# Sparkfun_MiP_ProMini-Pack.net
KiCad netlist of a schematic drawn in EAGLE
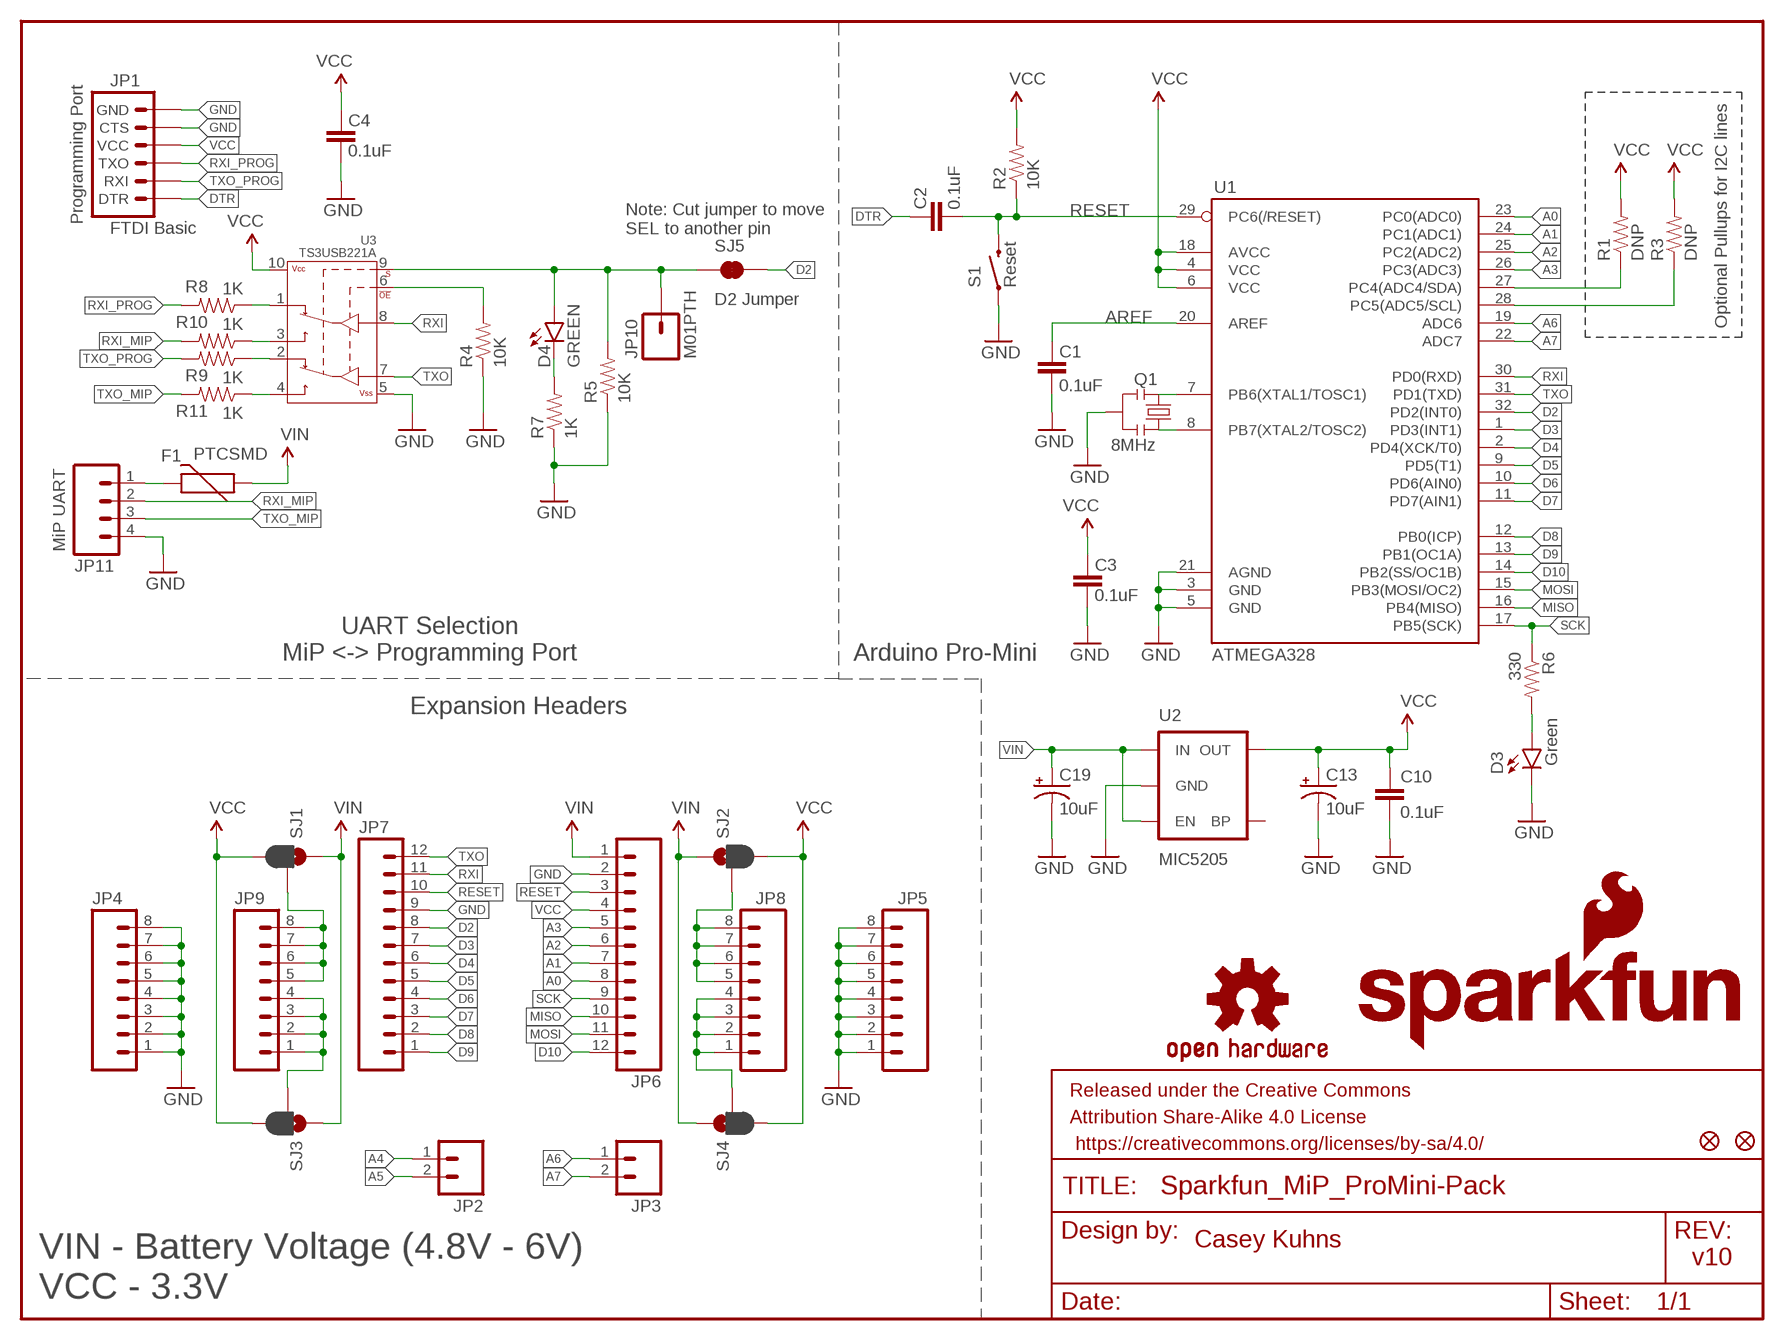
[diagram p0: schematic, sheet 1]

(export (version "E")
  (design (tool "Eeschema 10.0.6"))
  (components
    (comp (ref "C1")
      (value "0.1uF")
      (footprint "eagle-import:0603-CAP")
      (libsource (lib "eagle-import") (part "0.1UF-25V(+80/-20%)(0603)"))
    )
    (comp (ref "C2")
      (value "0.1uF")
      (footprint "eagle-import:0603-CAP")
      (libsource (lib "eagle-import") (part "0.1UF-25V(+80/-20%)(0603)"))
    )
    (comp (ref "C3")
      (value "0.1uF")
      (footprint "eagle-import:0603-CAP")
      (libsource (lib "eagle-import") (part "0.1UF-25V(+80/-20%)(0603)"))
    )
    (comp (ref "C4")
      (value "0.1uF")
      (footprint "eagle-import:0603-CAP")
      (libsource (lib "eagle-import") (part "0.1UF-25V(+80/-20%)(0603)"))
    )
    (comp (ref "C10")
      (value "0.1uF")
      (footprint "eagle-import:0603-CAP")
      (libsource (lib "eagle-import") (part "0.1UF-25V(+80/-20%)(0603)"))
    )
    (comp (ref "C13")
      (value "10uF")
      (footprint "eagle-import:EIA3216")
      (libsource (lib "eagle-import") (part "CAP_POL1206"))
    )
    (comp (ref "C19")
      (value "10uF")
      (footprint "eagle-import:EIA3216")
      (libsource (lib "eagle-import") (part "CAP_POL1206"))
    )
    (comp (ref "D3")
      (value "Green")
      (footprint "eagle-import:LED-0603")
      (libsource (lib "eagle-import") (part "LED-GREEN0603"))
    )
    (comp (ref "D4")
      (value "GREEN")
      (footprint "eagle-import:LED-0603")
      (libsource (lib "eagle-import") (part "LED-GREEN0603"))
    )
    (comp (ref "F1")
      (value "PTCSMD")
      (footprint "eagle-import:PTC-1206")
      (libsource (lib "eagle-import") (part "PTCSMD"))
    )
    (comp (ref "FID1")
      (value "FIDUCIAL1X2")
      (footprint "eagle-import:FIDUCIAL-1X2")
      (libsource (lib "eagle-import") (part "FIDUCIAL1X2"))
    )
    (comp (ref "FID2")
      (value "FIDUCIAL1X2")
      (footprint "eagle-import:FIDUCIAL-1X2")
      (libsource (lib "eagle-import") (part "FIDUCIAL1X2"))
    )
    (comp (ref "FRAME1")
      (value "FRAME-LETTER")
      (footprint "eagle-import:CREATIVE_COMMONS")
      (libsource (lib "eagle-import") (part "FRAME-LETTER"))
    )
    (comp (ref "JP1")
      (value "FTDI Basic")
      (footprint "eagle-import:1X06")
      (libsource (lib "eagle-import") (part "ARDUINO_SERIAL_PROGRAMPTH"))
    )
    (comp (ref "JP2")
      (value "M02PTH")
      (footprint "eagle-import:1X02")
      (libsource (lib "eagle-import") (part "M02PTH"))
    )
    (comp (ref "JP3")
      (value "M02PTH")
      (footprint "eagle-import:1X02")
      (libsource (lib "eagle-import") (part "M02PTH"))
    )
    (comp (ref "JP4")
      (value "M081X08")
      (footprint "eagle-import:1X08")
      (libsource (lib "eagle-import") (part "M081X08"))
    )
    (comp (ref "JP5")
      (value "M081X08")
      (footprint "eagle-import:1X08")
      (libsource (lib "eagle-import") (part "M081X08"))
    )
    (comp (ref "JP6")
      (value "M12PTH")
      (footprint "eagle-import:1X12")
      (libsource (lib "eagle-import") (part "M12PTH"))
    )
    (comp (ref "JP7")
      (value "M12PTH")
      (footprint "eagle-import:1X12")
      (libsource (lib "eagle-import") (part "M12PTH"))
    )
    (comp (ref "JP8")
      (value "M081X08")
      (footprint "eagle-import:1X08")
      (libsource (lib "eagle-import") (part "M081X08"))
    )
    (comp (ref "JP9")
      (value "M081X08")
      (footprint "eagle-import:1X08")
      (libsource (lib "eagle-import") (part "M081X08"))
    )
    (comp (ref "JP10")
      (value "M01PTH")
      (footprint "eagle-import:1X01")
      (libsource (lib "eagle-import") (part "M01PTH"))
    )
    (comp (ref "JP11")
      (value "M04JST")
      (footprint "eagle-import:1X04-1.5MM_JST")
      (libsource (lib "eagle-import") (part "M04JST"))
    )
    (comp (ref "LOGO1")
      (value "SFE_LOGO_NAME_FLAME.1_INCH")
      (footprint "eagle-import:SFE_LOGO_NAME_FLAME_.1")
      (libsource (lib "eagle-import") (part "SFE_LOGO_NAME_FLAME.1_INCH"))
    )
    (comp (ref "LOGO2")
      (value "OSHW-LOGOS")
      (footprint "eagle-import:OSHW-LOGO-S")
      (libsource (lib "eagle-import") (part "OSHW-LOGOS"))
    )
    (comp (ref "Q1")
      (value "8MHz")
      (footprint "eagle-import:RESONATOR-SMD")
      (libsource (lib "eagle-import") (part "RESONATOR8MHZ"))
    )
    (comp (ref "R1")
      (value "DNP")
      (footprint "eagle-import:0603-RES")
      (libsource (lib "eagle-import") (part "RESISTOR0603-RES"))
    )
    (comp (ref "R2")
      (value "10K")
      (footprint "eagle-import:0603-RES")
      (libsource (lib "eagle-import") (part "RESISTOR0603-RES"))
    )
    (comp (ref "R3")
      (value "DNP")
      (footprint "eagle-import:0603-RES")
      (libsource (lib "eagle-import") (part "RESISTOR0603-RES"))
    )
    (comp (ref "R4")
      (value "10K")
      (footprint "eagle-import:0603-RES")
      (libsource (lib "eagle-import") (part "10KOHM1/10W1%(0603)0603"))
    )
    (comp (ref "R5")
      (value "10K")
      (footprint "eagle-import:0603-RES")
      (libsource (lib "eagle-import") (part "10KOHM1/10W1%(0603)0603"))
    )
    (comp (ref "R6")
      (value "330")
      (footprint "eagle-import:0603-RES")
      (libsource (lib "eagle-import") (part "330OHM1/10W1%(0603)"))
    )
    (comp (ref "R7")
      (value "1K")
      (footprint "eagle-import:0603-RES")
      (libsource (lib "eagle-import") (part "1KOHM1/10W1%(0603)"))
    )
    (comp (ref "R8")
      (value "1K")
      (footprint "eagle-import:0603-RES")
      (libsource (lib "eagle-import") (part "1KOHM1/10W1%(0603)"))
    )
    (comp (ref "R9")
      (value "1K")
      (footprint "eagle-import:0603-RES")
      (libsource (lib "eagle-import") (part "1KOHM1/10W1%(0603)"))
    )
    (comp (ref "R10")
      (value "1K")
      (footprint "eagle-import:0603-RES")
      (libsource (lib "eagle-import") (part "1KOHM1/10W1%(0603)"))
    )
    (comp (ref "R11")
      (value "1K")
      (footprint "eagle-import:0603-RES")
      (libsource (lib "eagle-import") (part "1KOHM1/10W1%(0603)"))
    )
    (comp (ref "S1")
      (value "Reset")
      (footprint "eagle-import:TACTILE-SWITCH-SMD")
      (libsource (lib "eagle-import") (part "SWITCH-MOMENTARY-2SMD"))
    )
    (comp (ref "SJ1")
      (value "JUMPER-PAD-3-2OF3_NC_BY_PASTE")
      (footprint "eagle-import:PAD-JUMPER-3-2OF3_NC_BY_PASTE_YES_SILK_FULL_BOX")
      (libsource (lib "eagle-import") (part "JUMPER-PAD-3-2OF3_NC_BY_PASTE"))
    )
    (comp (ref "SJ2")
      (value "JUMPER-PAD-3-2OF3_NC_BY_PASTE")
      (footprint "eagle-import:PAD-JUMPER-3-2OF3_NC_BY_PASTE_YES_SILK_FULL_BOX")
      (libsource (lib "eagle-import") (part "JUMPER-PAD-3-2OF3_NC_BY_PASTE"))
    )
    (comp (ref "SJ3")
      (value "JUMPER-PAD-3-2OF3_NC_BY_PASTE")
      (footprint "eagle-import:PAD-JUMPER-3-2OF3_NC_BY_PASTE_YES_SILK_FULL_BOX")
      (libsource (lib "eagle-import") (part "JUMPER-PAD-3-2OF3_NC_BY_PASTE"))
    )
    (comp (ref "SJ4")
      (value "JUMPER-PAD-3-2OF3_NC_BY_PASTE")
      (footprint "eagle-import:PAD-JUMPER-3-2OF3_NC_BY_PASTE_YES_SILK_FULL_BOX")
      (libsource (lib "eagle-import") (part "JUMPER-PAD-3-2OF3_NC_BY_PASTE"))
    )
    (comp (ref "SJ5")
      (value "D2 Jumper")
      (footprint "eagle-import:PAD-JUMPER-2-NC_BY_TRACE_YES_SILK")
      (libsource (lib "eagle-import") (part "JUMPER-PAD-2-NC_BY_TRACE"))
    )
    (comp (ref "U1")
      (value "ATMEGA328")
      (footprint "eagle-import:TQFP32-08")
      (libsource (lib "eagle-import") (part "ATMEGA328_SMT"))
    )
    (comp (ref "U2")
      (value "MIC5205")
      (footprint "eagle-import:SOT23-5")
      (libsource (lib "eagle-import") (part "MIC52053.3V"))
    )
    (comp (ref "U3")
      (value "TS3USB221A")
      (footprint "eagle-import:QFN-10-RSE")
      (libsource (lib "eagle-import") (part "TS3USB221A"))
    )
  )
  (nets
    (net (code "1") (name "/AREF") (class "Default")
      (node (ref "C1") (pin "2") (pinfunction "2_2") (pintype "passive"))
      (node (ref "U1") (pin "20") (pinfunction "AREF_20") (pintype "bidirectional"))
    )
    (net (code "2") (name "A0") (class "Default")
      (node (ref "JP6") (pin "8") (pinfunction "8_8") (pintype "passive"))
      (node (ref "U1") (pin "23") (pinfunction "PC0(ADC0)_23") (pintype "bidirectional"))
    )
    (net (code "3") (name "A1") (class "Default")
      (node (ref "JP6") (pin "7") (pinfunction "7_7") (pintype "passive"))
      (node (ref "U1") (pin "24") (pinfunction "PC1(ADC1)_24") (pintype "bidirectional"))
    )
    (net (code "4") (name "A2") (class "Default")
      (node (ref "JP6") (pin "6") (pinfunction "6_6") (pintype "passive"))
      (node (ref "U1") (pin "25") (pinfunction "PC2(ADC2)_25") (pintype "bidirectional"))
    )
    (net (code "5") (name "A3") (class "Default")
      (node (ref "JP6") (pin "5") (pinfunction "5_5") (pintype "passive"))
      (node (ref "U1") (pin "26") (pinfunction "PC3(ADC3)_26") (pintype "bidirectional"))
    )
    (net (code "6") (name "A4") (class "Default")
      (node (ref "JP2") (pin "1") (pinfunction "1_1") (pintype "passive"))
      (node (ref "R1") (pin "1") (pinfunction "1_1") (pintype "passive"))
      (node (ref "U1") (pin "27") (pinfunction "PC4(ADC4/SDA)_27") (pintype "bidirectional"))
    )
    (net (code "7") (name "A5") (class "Default")
      (node (ref "JP2") (pin "2") (pinfunction "2_2") (pintype "passive"))
      (node (ref "R3") (pin "1") (pinfunction "1_1") (pintype "passive"))
      (node (ref "U1") (pin "28") (pinfunction "PC5(ADC5/SCL)_28") (pintype "bidirectional"))
    )
    (net (code "8") (name "A6") (class "Default")
      (node (ref "JP3") (pin "1") (pinfunction "1_1") (pintype "passive"))
      (node (ref "U1") (pin "19") (pinfunction "ADC6_19") (pintype "bidirectional"))
    )
    (net (code "9") (name "A7") (class "Default")
      (node (ref "JP3") (pin "2") (pinfunction "2_2") (pintype "passive"))
      (node (ref "U1") (pin "22") (pinfunction "ADC7_22") (pintype "bidirectional"))
    )
    (net (code "10") (name "D2") (class "Default")
      (node (ref "JP7") (pin "8") (pinfunction "8_8") (pintype "passive"))
      (node (ref "SJ5") (pin "2") (pinfunction "2_2") (pintype "passive"))
      (node (ref "U1") (pin "32") (pinfunction "PD2(INT0)_32") (pintype "bidirectional"))
    )
    (net (code "11") (name "D3") (class "Default")
      (node (ref "JP7") (pin "7") (pinfunction "7_7") (pintype "passive"))
      (node (ref "U1") (pin "1") (pinfunction "PD3(INT1)_1") (pintype "bidirectional"))
    )
    (net (code "12") (name "D4") (class "Default")
      (node (ref "JP7") (pin "6") (pinfunction "6_6") (pintype "passive"))
      (node (ref "U1") (pin "2") (pinfunction "PD4(XCK/T0)_2") (pintype "bidirectional"))
    )
    (net (code "13") (name "D5") (class "Default")
      (node (ref "JP7") (pin "5") (pinfunction "5_5") (pintype "passive"))
      (node (ref "U1") (pin "9") (pinfunction "PD5(T1)_9") (pintype "bidirectional"))
    )
    (net (code "14") (name "D6") (class "Default")
      (node (ref "JP7") (pin "4") (pinfunction "4_4") (pintype "passive"))
      (node (ref "U1") (pin "10") (pinfunction "PD6(AIN0)_10") (pintype "bidirectional"))
    )
    (net (code "15") (name "D7") (class "Default")
      (node (ref "JP7") (pin "3") (pinfunction "3_3") (pintype "passive"))
      (node (ref "U1") (pin "11") (pinfunction "PD7(AIN1)_11") (pintype "bidirectional"))
    )
    (net (code "16") (name "D8") (class "Default")
      (node (ref "JP7") (pin "2") (pinfunction "2_2") (pintype "passive"))
      (node (ref "U1") (pin "12") (pinfunction "PB0(ICP)_12") (pintype "bidirectional"))
    )
    (net (code "17") (name "D9") (class "Default")
      (node (ref "JP7") (pin "1") (pinfunction "1_1") (pintype "passive"))
      (node (ref "U1") (pin "13") (pinfunction "PB1(OC1A)_13") (pintype "bidirectional"))
    )
    (net (code "18") (name "D10") (class "Default")
      (node (ref "JP6") (pin "12") (pinfunction "12_12") (pintype "passive"))
      (node (ref "U1") (pin "14") (pinfunction "PB2(SS/OC1B)_14") (pintype "bidirectional"))
    )
    (net (code "19") (name "DTR") (class "Default")
      (node (ref "C2") (pin "2") (pinfunction "2_2") (pintype "passive"))
      (node (ref "JP1") (pin "1") (pinfunction "DTR_1") (pintype "passive"))
    )
    (net (code "20") (name "GND") (class "Default")
      (node (ref "C1") (pin "1") (pinfunction "1_1") (pintype "passive"))
      (node (ref "C10") (pin "2") (pinfunction "2_2") (pintype "passive"))
      (node (ref "C13") (pin "C") (pinfunction "-_C") (pintype "passive"))
      (node (ref "C19") (pin "C") (pinfunction "-_C") (pintype "passive"))
      (node (ref "C3") (pin "1") (pinfunction "1_1") (pintype "passive"))
      (node (ref "C4") (pin "1") (pinfunction "1_1") (pintype "passive"))
      (node (ref "D3") (pin "C") (pinfunction "C_C") (pintype "passive"))
      (node (ref "JP1") (pin "5") (pinfunction "CTS_5") (pintype "passive"))
      (node (ref "JP1") (pin "6") (pinfunction "GND_6") (pintype "passive"))
      (node (ref "JP11") (pin "4") (pinfunction "4_4") (pintype "passive"))
      (node (ref "JP4") (pin "1") (pinfunction "1_1") (pintype "passive"))
      (node (ref "JP4") (pin "2") (pinfunction "2_2") (pintype "passive"))
      (node (ref "JP4") (pin "3") (pinfunction "3_3") (pintype "passive"))
      (node (ref "JP4") (pin "4") (pinfunction "4_4") (pintype "passive"))
      (node (ref "JP4") (pin "5") (pinfunction "5_5") (pintype "passive"))
      (node (ref "JP4") (pin "6") (pinfunction "6_6") (pintype "passive"))
      (node (ref "JP4") (pin "7") (pinfunction "7_7") (pintype "passive"))
      (node (ref "JP4") (pin "8") (pinfunction "8_8") (pintype "passive"))
      (node (ref "JP5") (pin "1") (pinfunction "1_1") (pintype "passive"))
      (node (ref "JP5") (pin "2") (pinfunction "2_2") (pintype "passive"))
      (node (ref "JP5") (pin "3") (pinfunction "3_3") (pintype "passive"))
      (node (ref "JP5") (pin "4") (pinfunction "4_4") (pintype "passive"))
      (node (ref "JP5") (pin "5") (pinfunction "5_5") (pintype "passive"))
      (node (ref "JP5") (pin "6") (pinfunction "6_6") (pintype "passive"))
      (node (ref "JP5") (pin "7") (pinfunction "7_7") (pintype "passive"))
      (node (ref "JP5") (pin "8") (pinfunction "8_8") (pintype "passive"))
      (node (ref "JP6") (pin "2") (pinfunction "2_2") (pintype "passive"))
      (node (ref "JP7") (pin "9") (pinfunction "9_9") (pintype "passive"))
      (node (ref "Q1") (pin "2") (pinfunction "2_2") (pintype "passive"))
      (node (ref "R4") (pin "1") (pinfunction "1_1") (pintype "passive"))
      (node (ref "R5") (pin "1") (pinfunction "1_1") (pintype "passive"))
      (node (ref "R7") (pin "1") (pinfunction "1_1") (pintype "passive"))
      (node (ref "S1") (pin "1") (pinfunction "1_1") (pintype "passive"))
      (node (ref "U1") (pin "21") (pinfunction "AGND_21") (pintype "bidirectional"))
      (node (ref "U1") (pin "3") (pinfunction "GND_3") (pintype "bidirectional"))
      (node (ref "U1") (pin "5") (pinfunction "GND_5") (pintype "bidirectional"))
      (node (ref "U2") (pin "2") (pinfunction "GND_2") (pintype "input"))
      (node (ref "U3") (pin "5") (pinfunction "VSS_5") (pintype "bidirectional"))
    )
    (net (code "21") (name "MISO") (class "Default")
      (node (ref "JP6") (pin "10") (pinfunction "10_10") (pintype "passive"))
      (node (ref "U1") (pin "16") (pinfunction "PB4(MISO)_16") (pintype "bidirectional"))
    )
    (net (code "22") (name "MOSI") (class "Default")
      (node (ref "JP6") (pin "11") (pinfunction "11_11") (pintype "passive"))
      (node (ref "U1") (pin "15") (pinfunction "PB3(MOSI/OC2)_15") (pintype "bidirectional"))
    )
    (net (code "23") (name "Net-(D3-PadA)") (class "Default")
      (node (ref "D3") (pin "A") (pinfunction "A_A") (pintype "passive"))
      (node (ref "R6") (pin "2") (pinfunction "2_2") (pintype "passive"))
    )
    (net (code "24") (name "Net-(D4-PadC)") (class "Default")
      (node (ref "D4") (pin "C") (pinfunction "C_C") (pintype "passive"))
      (node (ref "R7") (pin "2") (pinfunction "2_2") (pintype "passive"))
    )
    (net (code "25") (name "Net-(F1-Pad2)") (class "Default")
      (node (ref "F1") (pin "2") (pinfunction "2_2") (pintype "bidirectional"))
      (node (ref "JP11") (pin "1") (pinfunction "1_1") (pintype "passive"))
    )
    (net (code "26") (name "Net-(JP8-Pad1)") (class "Default")
      (node (ref "JP8") (pin "1") (pinfunction "1_1") (pintype "passive"))
      (node (ref "JP8") (pin "2") (pinfunction "2_2") (pintype "passive"))
      (node (ref "JP8") (pin "3") (pinfunction "3_3") (pintype "passive"))
      (node (ref "JP8") (pin "4") (pinfunction "4_4") (pintype "passive"))
      (node (ref "SJ4") (pin "2") (pinfunction "2_2") (pintype "passive"))
    )
    (net (code "27") (name "Net-(JP8-Pad5)") (class "Default")
      (node (ref "JP8") (pin "5") (pinfunction "5_5") (pintype "passive"))
      (node (ref "JP8") (pin "6") (pinfunction "6_6") (pintype "passive"))
      (node (ref "JP8") (pin "7") (pinfunction "7_7") (pintype "passive"))
      (node (ref "JP8") (pin "8") (pinfunction "8_8") (pintype "passive"))
      (node (ref "SJ2") (pin "2") (pinfunction "2_2") (pintype "passive"))
    )
    (net (code "28") (name "Net-(JP9-Pad1)") (class "Default")
      (node (ref "JP9") (pin "1") (pinfunction "1_1") (pintype "passive"))
      (node (ref "JP9") (pin "2") (pinfunction "2_2") (pintype "passive"))
      (node (ref "JP9") (pin "3") (pinfunction "3_3") (pintype "passive"))
      (node (ref "JP9") (pin "4") (pinfunction "4_4") (pintype "passive"))
      (node (ref "SJ3") (pin "2") (pinfunction "2_2") (pintype "passive"))
    )
    (net (code "29") (name "Net-(JP9-Pad5)") (class "Default")
      (node (ref "JP9") (pin "5") (pinfunction "5_5") (pintype "passive"))
      (node (ref "JP9") (pin "6") (pinfunction "6_6") (pintype "passive"))
      (node (ref "JP9") (pin "7") (pinfunction "7_7") (pintype "passive"))
      (node (ref "JP9") (pin "8") (pinfunction "8_8") (pintype "passive"))
      (node (ref "SJ1") (pin "2") (pinfunction "2_2") (pintype "passive"))
    )
    (net (code "30") (name "Net-(U1-PB6(XTAL1{slash}TOSC1))") (class "Default")
      (node (ref "Q1") (pin "1") (pinfunction "1_1") (pintype "passive"))
      (node (ref "U1") (pin "7") (pinfunction "PB6(XTAL1/TOSC1)_7") (pintype "bidirectional"))
    )
    (net (code "31") (name "Net-(U1-PB7(XTAL2{slash}TOSC2))") (class "Default")
      (node (ref "Q1") (pin "3") (pinfunction "3_3") (pintype "passive"))
      (node (ref "U1") (pin "8") (pinfunction "PB7(XTAL2/TOSC2)_8") (pintype "bidirectional"))
    )
    (net (code "32") (name "Net-(U3-1D+)") (class "Default")
      (node (ref "R8") (pin "1") (pinfunction "1_1") (pintype "passive"))
      (node (ref "U3") (pin "1") (pinfunction "1D+_1") (pintype "bidirectional"))
    )
    (net (code "33") (name "Net-(U3-1D-)") (class "Default")
      (node (ref "R9") (pin "1") (pinfunction "1_1") (pintype "passive"))
      (node (ref "U3") (pin "2") (pinfunction "1D-_2") (pintype "bidirectional"))
    )
    (net (code "34") (name "Net-(U3-2D+)") (class "Default")
      (node (ref "R10") (pin "1") (pinfunction "1_1") (pintype "passive"))
      (node (ref "U3") (pin "3") (pinfunction "2D+_3") (pintype "bidirectional"))
    )
    (net (code "35") (name "Net-(U3-2D-)") (class "Default")
      (node (ref "R11") (pin "1") (pinfunction "1_1") (pintype "passive"))
      (node (ref "U3") (pin "4") (pinfunction "2D-_4") (pintype "bidirectional"))
    )
    (net (code "36") (name "Net-(U3-S)") (class "Default")
      (node (ref "D4") (pin "A") (pinfunction "A_A") (pintype "passive"))
      (node (ref "JP10") (pin "1") (pinfunction "1_1") (pintype "passive"))
      (node (ref "R5") (pin "2") (pinfunction "2_2") (pintype "passive"))
      (node (ref "SJ5") (pin "1") (pinfunction "1_1") (pintype "passive"))
      (node (ref "U3") (pin "9") (pinfunction "S_9") (pintype "bidirectional"))
    )
    (net (code "37") (name "Net-(U3-~{OE})") (class "Default")
      (node (ref "R4") (pin "2") (pinfunction "2_2") (pintype "passive"))
      (node (ref "U3") (pin "6") (pinfunction "~{OE}_6") (pintype "bidirectional"))
    )
    (net (code "38") (name "RESET") (class "Default")
      (node (ref "C2") (pin "1") (pinfunction "1_1") (pintype "passive"))
      (node (ref "JP6") (pin "3") (pinfunction "3_3") (pintype "passive"))
      (node (ref "JP7") (pin "10") (pinfunction "10_10") (pintype "passive"))
      (node (ref "R2") (pin "1") (pinfunction "1_1") (pintype "passive"))
      (node (ref "S1") (pin "3") (pinfunction "2_3") (pintype "passive"))
      (node (ref "U1") (pin "29") (pinfunction "PC6(/RESET)_29") (pintype "bidirectional"))
    )
    (net (code "39") (name "RXI") (class "Default")
      (node (ref "JP7") (pin "11") (pinfunction "11_11") (pintype "passive"))
      (node (ref "U1") (pin "30") (pinfunction "PD0(RXD)_30") (pintype "bidirectional"))
      (node (ref "U3") (pin "8") (pinfunction "D+_8") (pintype "bidirectional"))
    )
    (net (code "40") (name "RXI_MIP") (class "Default")
      (node (ref "JP11") (pin "2") (pinfunction "2_2") (pintype "passive"))
      (node (ref "R10") (pin "2") (pinfunction "2_2") (pintype "passive"))
    )
    (net (code "41") (name "RXI_PROG") (class "Default")
      (node (ref "JP1") (pin "3") (pinfunction "TXO_3") (pintype "passive"))
      (node (ref "R8") (pin "2") (pinfunction "2_2") (pintype "passive"))
    )
    (net (code "42") (name "SCK") (class "Default")
      (node (ref "JP6") (pin "9") (pinfunction "9_9") (pintype "passive"))
      (node (ref "R6") (pin "1") (pinfunction "1_1") (pintype "passive"))
      (node (ref "U1") (pin "17") (pinfunction "PB5(SCK)_17") (pintype "bidirectional"))
    )
    (net (code "43") (name "TXO") (class "Default")
      (node (ref "JP7") (pin "12") (pinfunction "12_12") (pintype "passive"))
      (node (ref "U1") (pin "31") (pinfunction "PD1(TXD)_31") (pintype "bidirectional"))
      (node (ref "U3") (pin "7") (pinfunction "D-_7") (pintype "bidirectional"))
    )
    (net (code "44") (name "TXO_MIP") (class "Default")
      (node (ref "JP11") (pin "3") (pinfunction "3_3") (pintype "passive"))
      (node (ref "R11") (pin "2") (pinfunction "2_2") (pintype "passive"))
    )
    (net (code "45") (name "TXO_PROG") (class "Default")
      (node (ref "JP1") (pin "2") (pinfunction "RXI_2") (pintype "passive"))
      (node (ref "R9") (pin "2") (pinfunction "2_2") (pintype "passive"))
    )
    (net (code "46") (name "VCC") (class "Default")
      (node (ref "C10") (pin "1") (pinfunction "1_1") (pintype "passive"))
      (node (ref "C13") (pin "A") (pinfunction "+_A") (pintype "passive"))
      (node (ref "C3") (pin "2") (pinfunction "2_2") (pintype "passive"))
      (node (ref "C4") (pin "2") (pinfunction "2_2") (pintype "passive"))
      (node (ref "JP1") (pin "4") (pinfunction "VCC_4") (pintype "passive"))
      (node (ref "JP6") (pin "4") (pinfunction "4_4") (pintype "passive"))
      (node (ref "R1") (pin "2") (pinfunction "2_2") (pintype "passive"))
      (node (ref "R2") (pin "2") (pinfunction "2_2") (pintype "passive"))
      (node (ref "R3") (pin "2") (pinfunction "2_2") (pintype "passive"))
      (node (ref "SJ1") (pin "3") (pinfunction "3_3") (pintype "passive"))
      (node (ref "SJ2") (pin "3") (pinfunction "3_3") (pintype "passive"))
      (node (ref "SJ3") (pin "3") (pinfunction "3_3") (pintype "passive"))
      (node (ref "SJ4") (pin "3") (pinfunction "3_3") (pintype "passive"))
      (node (ref "U1") (pin "18") (pinfunction "AVCC_18") (pintype "bidirectional"))
      (node (ref "U1") (pin "4") (pinfunction "VCC_4") (pintype "bidirectional"))
      (node (ref "U1") (pin "6") (pinfunction "VCC_6") (pintype "bidirectional"))
      (node (ref "U2") (pin "5") (pinfunction "OUT_5") (pintype "passive"))
      (node (ref "U3") (pin "10") (pinfunction "VCC_10") (pintype "bidirectional"))
    )
    (net (code "47") (name "VIN") (class "Default")
      (node (ref "C19") (pin "A") (pinfunction "+_A") (pintype "passive"))
      (node (ref "F1") (pin "1") (pinfunction "1_1") (pintype "bidirectional"))
      (node (ref "JP6") (pin "1") (pinfunction "1_1") (pintype "passive"))
      (node (ref "SJ1") (pin "1") (pinfunction "1_1") (pintype "passive"))
      (node (ref "SJ2") (pin "1") (pinfunction "1_1") (pintype "passive"))
      (node (ref "SJ3") (pin "1") (pinfunction "1_1") (pintype "passive"))
      (node (ref "SJ4") (pin "1") (pinfunction "1_1") (pintype "passive"))
      (node (ref "U2") (pin "1") (pinfunction "IN_1") (pintype "input"))
      (node (ref "U2") (pin "3") (pinfunction "EN_3") (pintype "input"))
    )
    (net (code "48") (name "unconnected-(U2-BP-Pad4)") (class "Default")
      (node (ref "U2") (pin "4") (pinfunction "BP_4") (pintype "input"))
    )
  )
)
